# MCU.net
KiCad netlist of a schematic drawn in Altium Designer
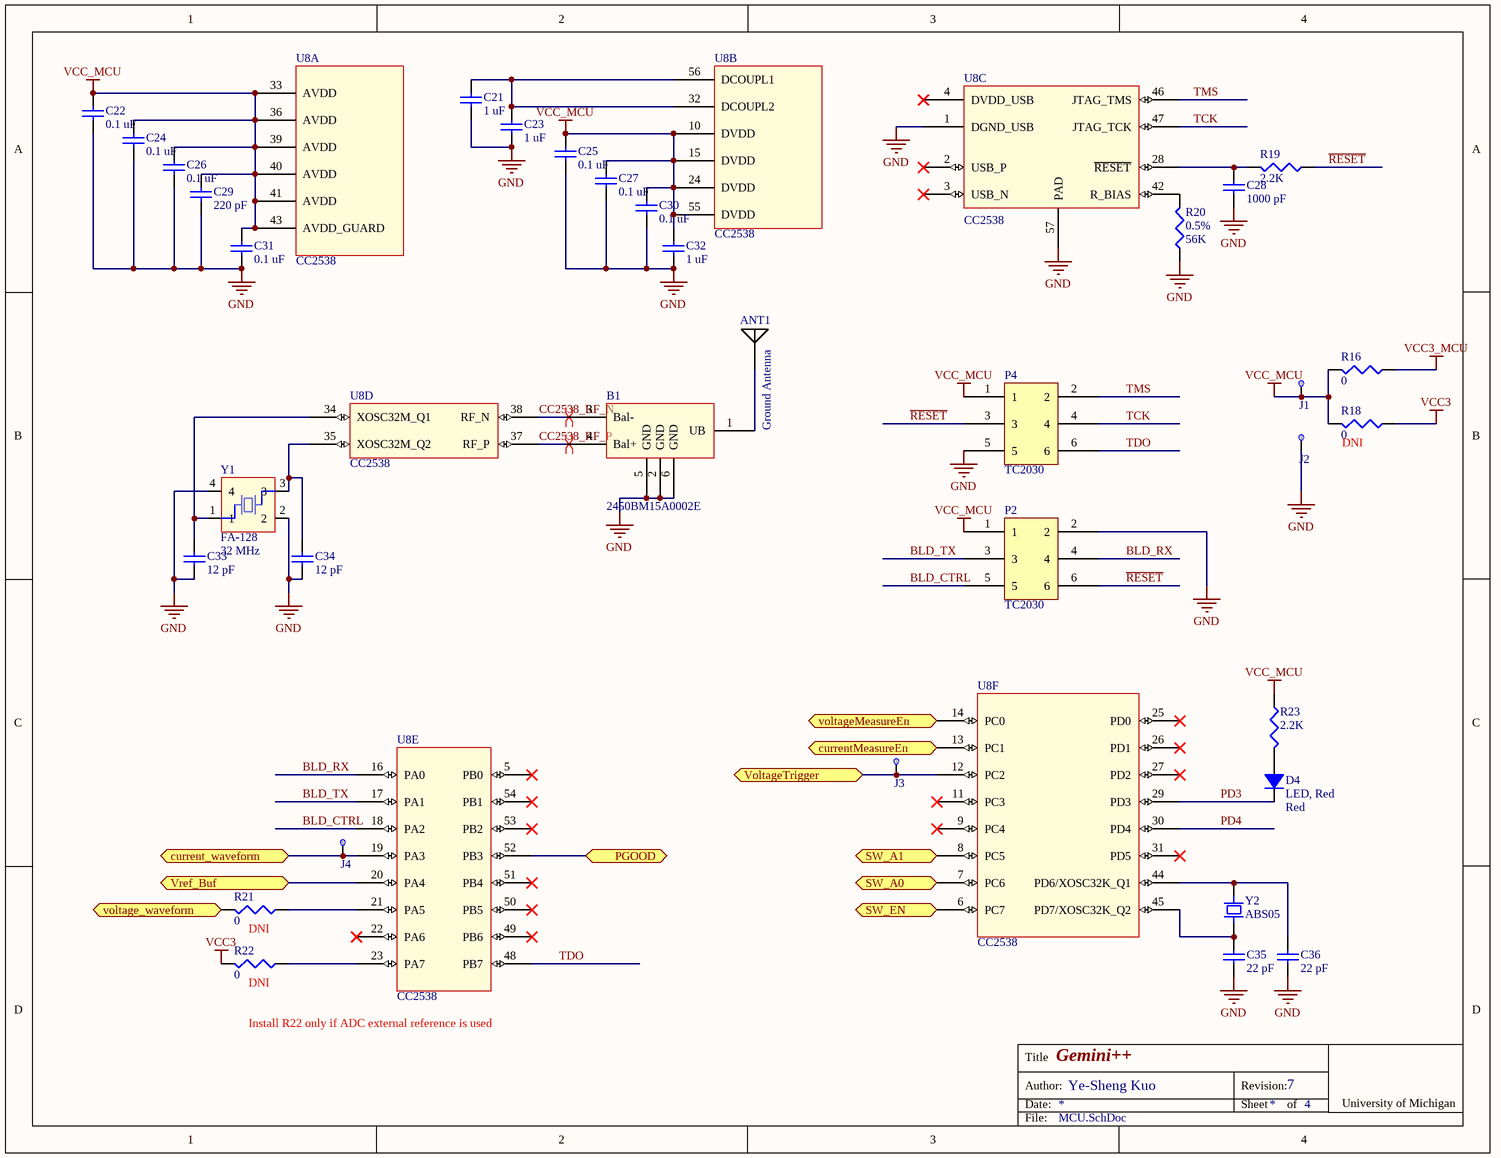
[diagram p0: MCU.SchDoc]

(export (version "E")
  (design (tool "Eeschema 10.0.6"))
  (components
    (comp (ref "ANT1")
      (value "Ground Antenna")
      (footprint "Chip Antenna")
      (description "2.4GHz Surface Mount Device (SMD) On Ground Antenna, 50 Ohms")
      (libsource (lib "RF") (part "Ground Antenna"))
    )
    (comp (ref "B1")
      (value "2450BM15A0002E")
      (footprint "2450BM15A0002")
      (description "2.45 GHz Balun for TI CC253X")
      (libsource (lib "RF") (part "2450BM15A0002E"))
    )
    (comp (ref "C21")
      (value "1 uF")
      (footprint "0402")
      (description "Ceramic capacitor, 1 uF, 16V, 0402 package")
      (fields (field (name "TOLERANCE") "10%") (field (name "Comment") "Ceramic capacitor"))
      (libsource (lib "rlc") (part "C_1u_16V_0402_ceramic"))
    )
    (comp (ref "C22")
      (value "0.1 uF")
      (footprint "0402")
      (description "Ceramic capacitor, 0.1u, 0402 package")
      (fields (field (name "TOLERANCE") "10%") (field (name "Comment") "Ceramic capacitor"))
      (libsource (lib "rlc") (part "C_0.1u_10V_0402_ceramic"))
    )
    (comp (ref "C23")
      (value "1 uF")
      (footprint "0402")
      (description "Ceramic capacitor, 1 uF, 16V, 0402 package")
      (fields (field (name "TOLERANCE") "10%") (field (name "Comment") "Ceramic capacitor"))
      (libsource (lib "rlc") (part "C_1u_16V_0402_ceramic"))
    )
    (comp (ref "C24")
      (value "0.1 uF")
      (footprint "0402")
      (description "Ceramic capacitor, 0.1u, 0402 package")
      (fields (field (name "TOLERANCE") "10%") (field (name "Comment") "Ceramic capacitor"))
      (libsource (lib "rlc") (part "C_0.1u_10V_0402_ceramic"))
    )
    (comp (ref "C25")
      (value "0.1 uF")
      (footprint "0402")
      (description "Ceramic capacitor, 0.1u, 0402 package")
      (fields (field (name "TOLERANCE") "10%") (field (name "Comment") "Ceramic capacitor"))
      (libsource (lib "rlc") (part "C_0.1u_10V_0402_ceramic"))
    )
    (comp (ref "C26")
      (value "0.1 uF")
      (footprint "0402")
      (description "Ceramic capacitor, 0.1u, 0402 package")
      (fields (field (name "TOLERANCE") "10%") (field (name "Comment") "Ceramic capacitor"))
      (libsource (lib "rlc") (part "C_0.1u_10V_0402_ceramic"))
    )
    (comp (ref "C27")
      (value "0.1 uF")
      (footprint "0402")
      (description "Ceramic capacitor, 0.1u, 0402 package")
      (fields (field (name "TOLERANCE") "10%") (field (name "Comment") "Ceramic capacitor"))
      (libsource (lib "rlc") (part "C_0.1u_10V_0402_ceramic"))
    )
    (comp (ref "C28")
      (value "1000 pF")
      (footprint "0402")
      (description "Ceramic capacitor, 1000 pF, 0402 package")
      (fields (field (name "TOLERANCE") "10%") (field (name "Comment") "Ceramic capacitor"))
      (libsource (lib "rlc") (part "C_1000p_50V_0402_ceramic"))
    )
    (comp (ref "C29")
      (value "220 pF")
      (footprint "0402")
      (description "Ceramic capacitor, 220 pF, 0402 package")
      (fields (field (name "TOLERANCE") "10%") (field (name "Comment") "Ceramic capacitor"))
      (libsource (lib "rlc") (part "C_220p_50V_0402_ceramic"))
    )
    (comp (ref "C30")
      (value "0.1 uF")
      (footprint "0402")
      (description "Ceramic capacitor, 0.1u, 0402 package")
      (fields (field (name "TOLERANCE") "10%") (field (name "Comment") "Ceramic capacitor"))
      (libsource (lib "rlc") (part "C_0.1u_10V_0402_ceramic"))
    )
    (comp (ref "C31")
      (value "0.1 uF")
      (footprint "0402")
      (description "Ceramic capacitor, 0.1u, 0402 package")
      (fields (field (name "TOLERANCE") "10%") (field (name "Comment") "Ceramic capacitor"))
      (libsource (lib "rlc") (part "C_0.1u_10V_0402_ceramic"))
    )
    (comp (ref "C32")
      (value "1 uF")
      (footprint "0402")
      (description "Ceramic capacitor, 1 uF, 16V, 0402 package")
      (fields (field (name "TOLERANCE") "10%") (field (name "Comment") "Ceramic capacitor"))
      (libsource (lib "rlc") (part "C_1u_16V_0402_ceramic"))
    )
    (comp (ref "C33")
      (value "12 pF")
      (footprint "0402")
      (description "Ceramic capacitor, 12 pF, 0402 package")
      (fields (field (name "TOLERANCE") "2%") (field (name "Comment") "Ceramic capacitor"))
      (libsource (lib "rlc") (part "C_12p_0402_ceramic"))
    )
    (comp (ref "C34")
      (value "12 pF")
      (footprint "0402")
      (description "Ceramic capacitor, 12 pF, 0402 package")
      (fields (field (name "TOLERANCE") "2%") (field (name "Comment") "Ceramic capacitor"))
      (libsource (lib "rlc") (part "C_12p_0402_ceramic"))
    )
    (comp (ref "C35")
      (value "22 pF")
      (footprint "0402")
      (description "Ceramic capacitor, 22 pF, 0402 package")
      (fields (field (name "TOLERANCE") "2%") (field (name "Comment") "Ceramic capacitor"))
      (libsource (lib "rlc") (part "C_22p_0402_ceramic"))
    )
    (comp (ref "C36")
      (value "22 pF")
      (footprint "0402")
      (description "Ceramic capacitor, 22 pF, 0402 package")
      (fields (field (name "TOLERANCE") "2%") (field (name "Comment") "Ceramic capacitor"))
      (libsource (lib "rlc") (part "C_22p_0402_ceramic"))
    )
    (comp (ref "D4")
      (value "LED, Red")
      (footprint "0402 - DIODE")
      (description "LED, Red, 0402")
      (fields (field (name "COLOR") "Red"))
      (libsource (lib "rlc") (part "D_LED_RED_0402"))
    )
    (comp (ref "J1")
      (value "RCU 0603 SMD Testpoint")
      (footprint "RCU_0603")
      (description "0603 SMD Testpoint")
      (libsource (lib "connectors") (part "Testpoint-0603"))
    )
    (comp (ref "J2")
      (value "RCU 0603 SMD Testpoint")
      (footprint "RCU_0603")
      (description "0603 SMD Testpoint")
      (libsource (lib "connectors") (part "Testpoint-0603"))
    )
    (comp (ref "J3")
      (value "RCU 0603 SMD Testpoint")
      (footprint "RCU_0603")
      (description "0603 SMD Testpoint")
      (libsource (lib "connectors") (part "Testpoint-0603"))
    )
    (comp (ref "J4")
      (value "RCU 0603 SMD Testpoint")
      (footprint "RCU_0603")
      (description "0603 SMD Testpoint")
      (libsource (lib "connectors") (part "Testpoint-0603"))
    )
    (comp (ref "P2")
      (value "TC2030")
      (footprint "TC2030-IDC-NLFP")
      (description "TC2030-MCP-NL")
      (libsource (lib "connectors") (part "TC2030"))
    )
    (comp (ref "P4")
      (value "TC2030")
      (footprint "TC2030-IDC-NLFP")
      (description "TC2030-MCP-NL")
      (libsource (lib "connectors") (part "TC2030"))
    )
    (comp (ref "R16")
      (value "0")
      (footprint "0603")
      (description "Chip resistor, 0, 0603 package")
      (fields (field (name "Comment") "Chip resistor"))
      (libsource (lib "rlc") (part "R_0_0603"))
    )
    (comp (ref "R18")
      (value "0")
      (footprint "0603")
      (description "Chip resistor, 0, 0603 package")
      (fields (field (name "Comment") "Chip resistor"))
      (libsource (lib "rlc") (part "R_0_0603"))
    )
    (comp (ref "R19")
      (value "2.2K")
      (footprint "0402")
      (description "Chip resistor, 2.2K, 0402 package")
      (fields (field (name "TOLERANCE") "1%") (field (name "POWER") "1/16 W"))
      (libsource (lib "rlc") (part "R_2.2K_0402"))
    )
    (comp (ref "R20")
      (value "56K")
      (footprint "0402")
      (description "Chip resistor, 56K, 0402 package")
      (fields
        (field (name "POWER") "1/16 W")
        (field (name "TOLERANCE") "0.5%")
        (field (name "Comment") "Chip resistor")
      )
      (libsource (lib "rlc") (part "R_56K_0402"))
    )
    (comp (ref "R21")
      (value "0")
      (footprint "0402")
      (description "Chip resistor, 0, 0402 package")
      (fields (field (name "Comment") "Chip resistor"))
      (libsource (lib "rlc") (part "R_0_0402"))
    )
    (comp (ref "R22")
      (value "0")
      (footprint "0402")
      (description "Chip resistor, 0, 0402 package")
      (fields (field (name "Comment") "Chip resistor"))
      (libsource (lib "rlc") (part "R_0_0402"))
    )
    (comp (ref "R23")
      (value "2.2K")
      (footprint "0402")
      (description "Chip resistor, 2.2K, 0402 package")
      (fields (field (name "TOLERANCE") "1%") (field (name "POWER") "1/16 W"))
      (libsource (lib "rlc") (part "R_2.2K_0402"))
    )
    (comp (ref "U8")
      (value "CC2538")
      (footprint "QFN56")
      (description "A Powerful System-On-Chip for 2.4-GHz IEEE 802.15.4, 6LoWPAN  and ZigBee Applications")
      (libsource (lib "sdl") (part "CC2538"))
    )
    (comp (ref "Y1")
      (value "FA-128")
      (footprint "FA-128")
      (description "MHz Range Crystal Unit")
      (fields (field (name "FREQUENCY") "32 MHz"))
      (libsource (lib "crystal_oscillators_rtc") (part "FA-128"))
    )
    (comp (ref "Y2")
      (value "ABS05")
      (footprint "ABS05")
      (description "32768 Hz SMD Low profile crystal")
      (libsource (lib "crystal_oscillators_rtc") (part "ABS05"))
    )
  )
  (nets
    (net (code "1") (name "/BLD_CTRL") (class "Default")
      (node (ref "P2") (pin "5") (pinfunction "5_5") (pintype "passive"))
      (node (ref "U8") (pin "18") (pinfunction "PA2_18") (pintype "bidirectional"))
    )
    (net (code "2") (name "/BLD_RX") (class "Default")
      (node (ref "P2") (pin "4") (pinfunction "4_4") (pintype "passive"))
      (node (ref "U8") (pin "16") (pinfunction "PA0_16") (pintype "bidirectional"))
    )
    (net (code "3") (name "/BLD_TX") (class "Default")
      (node (ref "P2") (pin "3") (pinfunction "3_3") (pintype "passive"))
      (node (ref "U8") (pin "17") (pinfunction "PA1_17") (pintype "bidirectional"))
    )
    (net (code "4") (name "/CC2538_RF_N") (class "Default")
      (node (ref "B1") (pin "3") (pinfunction "Bal-_3") (pintype "passive"))
      (node (ref "U8") (pin "38") (pinfunction "RF_N_38") (pintype "bidirectional"))
    )
    (net (code "5") (name "/CC2538_RF_P") (class "Default")
      (node (ref "B1") (pin "4") (pinfunction "Bal+_4") (pintype "passive"))
      (node (ref "U8") (pin "37") (pinfunction "RF_P_37") (pintype "bidirectional"))
    )
    (net (code "6") (name "/PD3") (class "Default")
      (node (ref "D4") (pin "2") (pintype "passive"))
      (node (ref "U8") (pin "29") (pinfunction "PD3_29") (pintype "bidirectional"))
    )
    (net (code "7") (name "/PD4") (class "Default")
      (node (ref "U8") (pin "30") (pinfunction "PD4_30") (pintype "bidirectional"))
    )
    (net (code "8") (name "/PGOOD") (class "Default")
      (node (ref "U8") (pin "52") (pinfunction "PB3_52") (pintype "bidirectional"))
    )
    (net (code "9") (name "/SW_A0") (class "Default")
      (node (ref "U8") (pin "7") (pinfunction "PC6_7") (pintype "bidirectional"))
    )
    (net (code "10") (name "/SW_A1") (class "Default")
      (node (ref "U8") (pin "8") (pinfunction "PC5_8") (pintype "bidirectional"))
    )
    (net (code "11") (name "/SW_EN") (class "Default")
      (node (ref "U8") (pin "6") (pinfunction "PC7_6") (pintype "bidirectional"))
    )
    (net (code "12") (name "/TCK") (class "Default")
      (node (ref "P4") (pin "4") (pinfunction "4_4") (pintype "passive"))
      (node (ref "U8") (pin "47") (pinfunction "JTAG_TCK_47") (pintype "bidirectional"))
    )
    (net (code "13") (name "/TDO") (class "Default")
      (node (ref "P4") (pin "6") (pinfunction "6_6") (pintype "passive"))
      (node (ref "U8") (pin "48") (pinfunction "PB7_48") (pintype "bidirectional"))
    )
    (net (code "14") (name "/TMS") (class "Default")
      (node (ref "P4") (pin "2") (pinfunction "2_2") (pintype "passive"))
      (node (ref "U8") (pin "46") (pinfunction "JTAG_TMS_46") (pintype "bidirectional"))
    )
    (net (code "15") (name "/VoltageTrigger") (class "Default")
      (node (ref "J3") (pin "1") (pinfunction "TB_1") (pintype "passive"))
      (node (ref "U8") (pin "12") (pinfunction "PC2_12") (pintype "bidirectional"))
    )
    (net (code "16") (name "/Vref_Buf") (class "Default")
      (node (ref "U8") (pin "20") (pinfunction "PA4_20") (pintype "bidirectional"))
    )
    (net (code "17") (name "/currentMeasureEn") (class "Default")
      (node (ref "U8") (pin "13") (pinfunction "PC1_13") (pintype "bidirectional"))
    )
    (net (code "18") (name "/current_waveform") (class "Default")
      (node (ref "J4") (pin "1") (pinfunction "TB_1") (pintype "passive"))
      (node (ref "U8") (pin "19") (pinfunction "PA3_19") (pintype "bidirectional"))
    )
    (net (code "19") (name "/voltageMeasureEn") (class "Default")
      (node (ref "U8") (pin "14") (pinfunction "PC0_14") (pintype "bidirectional"))
    )
    (net (code "20") (name "/voltage_waveform") (class "Default")
      (node (ref "R21") (pin "1") (pintype "passive"))
    )
    (net (code "21") (name "/~{RESET}") (class "Default")
      (node (ref "P2") (pin "6") (pinfunction "6_6") (pintype "passive"))
      (node (ref "P4") (pin "3") (pinfunction "3_3") (pintype "passive"))
      (node (ref "R19") (pin "2") (pintype "passive"))
    )
    (net (code "22") (name "GND") (class "Default")
      (node (ref "B1") (pin "2") (pinfunction "GND_2") (pintype "passive"))
      (node (ref "B1") (pin "5") (pinfunction "GND_5") (pintype "passive"))
      (node (ref "B1") (pin "6") (pinfunction "GND_6") (pintype "passive"))
      (node (ref "C21") (pin "2") (pintype "passive"))
      (node (ref "C22") (pin "2") (pintype "passive"))
      (node (ref "C23") (pin "2") (pintype "passive"))
      (node (ref "C24") (pin "2") (pintype "passive"))
      (node (ref "C25") (pin "2") (pintype "passive"))
      (node (ref "C26") (pin "2") (pintype "passive"))
      (node (ref "C27") (pin "2") (pintype "passive"))
      (node (ref "C28") (pin "2") (pintype "passive"))
      (node (ref "C29") (pin "2") (pintype "passive"))
      (node (ref "C30") (pin "2") (pintype "passive"))
      (node (ref "C31") (pin "2") (pintype "passive"))
      (node (ref "C32") (pin "2") (pintype "passive"))
      (node (ref "C33") (pin "1") (pintype "passive"))
      (node (ref "C34") (pin "1") (pintype "passive"))
      (node (ref "C35") (pin "2") (pintype "passive"))
      (node (ref "C36") (pin "2") (pintype "passive"))
      (node (ref "J2") (pin "1") (pinfunction "TB_1") (pintype "passive"))
      (node (ref "P2") (pin "2") (pinfunction "2_2") (pintype "passive"))
      (node (ref "P4") (pin "5") (pinfunction "5_5") (pintype "passive"))
      (node (ref "R20") (pin "2") (pintype "passive"))
      (node (ref "U8") (pin "1") (pinfunction "DGND_USB_1") (pintype "power_in"))
      (node (ref "U8") (pin "57") (pinfunction "PAD_57") (pintype "power_in"))
      (node (ref "Y1") (pin "2") (pinfunction "2_2") (pintype "passive"))
      (node (ref "Y1") (pin "4") (pinfunction "4_4") (pintype "passive"))
    )
    (net (code "23") (name "Net-(B1-UB)") (class "Default")
      (node (ref "ANT1") (pin "1") (pintype "passive"))
      (node (ref "B1") (pin "1") (pinfunction "UB_1") (pintype "passive"))
    )
    (net (code "24") (name "Net-(D4-Pad1)") (class "Default")
      (node (ref "D4") (pin "1") (pintype "passive"))
      (node (ref "R23") (pin "1") (pintype "passive"))
    )
    (net (code "25") (name "Net-(U8B-DCOUPL1)") (class "Default")
      (node (ref "C21") (pin "1") (pintype "passive"))
      (node (ref "C23") (pin "1") (pintype "passive"))
      (node (ref "U8") (pin "32") (pinfunction "DCOUPL2_32") (pintype "power_in"))
      (node (ref "U8") (pin "56") (pinfunction "DCOUPL1_56") (pintype "power_in"))
    )
    (net (code "26") (name "Net-(U8C-R_BIAS)") (class "Default")
      (node (ref "R20") (pin "1") (pintype "passive"))
      (node (ref "U8") (pin "42") (pinfunction "R_BIAS_42") (pintype "bidirectional"))
    )
    (net (code "27") (name "Net-(U8C-~{RESET})") (class "Default")
      (node (ref "C28") (pin "1") (pintype "passive"))
      (node (ref "R19") (pin "1") (pintype "passive"))
      (node (ref "U8") (pin "28") (pinfunction "~{RESET}_28") (pintype "bidirectional"))
    )
    (net (code "28") (name "Net-(U8D-XOSC32M_Q1)") (class "Default")
      (node (ref "C33") (pin "2") (pintype "passive"))
      (node (ref "U8") (pin "34") (pinfunction "XOSC32M_Q1_34") (pintype "bidirectional"))
      (node (ref "Y1") (pin "1") (pinfunction "1_1") (pintype "passive"))
    )
    (net (code "29") (name "Net-(U8D-XOSC32M_Q2)") (class "Default")
      (node (ref "C34") (pin "2") (pintype "passive"))
      (node (ref "U8") (pin "35") (pinfunction "XOSC32M_Q2_35") (pintype "bidirectional"))
      (node (ref "Y1") (pin "3") (pinfunction "3_3") (pintype "passive"))
    )
    (net (code "30") (name "Net-(U8E-PA5)") (class "Default")
      (node (ref "R21") (pin "2") (pintype "passive"))
      (node (ref "U8") (pin "21") (pinfunction "PA5_21") (pintype "bidirectional"))
    )
    (net (code "31") (name "Net-(U8E-PA7)") (class "Default")
      (node (ref "R22") (pin "2") (pintype "passive"))
      (node (ref "U8") (pin "23") (pinfunction "PA7_23") (pintype "bidirectional"))
    )
    (net (code "32") (name "Net-(U8F-PD6{slash}XOSC32K_Q1)") (class "Default")
      (node (ref "C36") (pin "1") (pintype "passive"))
      (node (ref "U8") (pin "44") (pinfunction "PD6/XOSC32K_Q1_44") (pintype "bidirectional"))
      (node (ref "Y2") (pin "1") (pintype "passive"))
    )
    (net (code "33") (name "Net-(U8F-PD7{slash}XOSC32K_Q2)") (class "Default")
      (node (ref "C35") (pin "1") (pintype "passive"))
      (node (ref "U8") (pin "45") (pinfunction "PD7/XOSC32K_Q2_45") (pintype "bidirectional"))
      (node (ref "Y2") (pin "2") (pintype "passive"))
    )
    (net (code "34") (name "VCC3") (class "Default")
      (node (ref "R18") (pin "2") (pintype "passive"))
      (node (ref "R22") (pin "1") (pintype "passive"))
    )
    (net (code "35") (name "VCC3_MCU") (class "Default") (node (ref "R16") (pin "2") (pintype "passive")))
    (net (code "36") (name "VCC_MCU") (class "Default")
      (node (ref "C22") (pin "1") (pintype "passive"))
      (node (ref "C24") (pin "1") (pintype "passive"))
      (node (ref "C25") (pin "1") (pintype "passive"))
      (node (ref "C26") (pin "1") (pintype "passive"))
      (node (ref "C27") (pin "1") (pintype "passive"))
      (node (ref "C29") (pin "1") (pintype "passive"))
      (node (ref "C30") (pin "1") (pintype "passive"))
      (node (ref "C31") (pin "1") (pintype "passive"))
      (node (ref "C32") (pin "1") (pintype "passive"))
      (node (ref "J1") (pin "1") (pinfunction "TB_1") (pintype "passive"))
      (node (ref "P2") (pin "1") (pinfunction "1_1") (pintype "passive"))
      (node (ref "P4") (pin "1") (pinfunction "1_1") (pintype "passive"))
      (node (ref "R16") (pin "1") (pintype "passive"))
      (node (ref "R18") (pin "1") (pintype "passive"))
      (node (ref "R23") (pin "2") (pintype "passive"))
      (node (ref "U8") (pin "10") (pinfunction "DVDD_10") (pintype "power_in"))
      (node (ref "U8") (pin "15") (pinfunction "DVDD_15") (pintype "power_in"))
      (node (ref "U8") (pin "24") (pinfunction "DVDD_24") (pintype "power_in"))
      (node (ref "U8") (pin "33") (pinfunction "AVDD_33") (pintype "power_in"))
      (node (ref "U8") (pin "36") (pinfunction "AVDD_36") (pintype "power_in"))
      (node (ref "U8") (pin "39") (pinfunction "AVDD_39") (pintype "power_in"))
      (node (ref "U8") (pin "40") (pinfunction "AVDD_40") (pintype "power_in"))
      (node (ref "U8") (pin "41") (pinfunction "AVDD_41") (pintype "power_in"))
      (node (ref "U8") (pin "43") (pinfunction "AVDD_GUARD_43") (pintype "power_in"))
      (node (ref "U8") (pin "55") (pinfunction "DVDD_55") (pintype "power_in"))
    )
    (net (code "37") (name "unconnected-(U8C-DVDD_USB-Pad4)") (class "Default")
      (node (ref "U8") (pin "4") (pinfunction "DVDD_USB_4") (pintype "power_in+no_connect"))
    )
    (net (code "38") (name "unconnected-(U8C-USB_N-Pad3)") (class "Default")
      (node (ref "U8") (pin "3") (pinfunction "USB_N_3") (pintype "bidirectional+no_connect"))
    )
    (net (code "39") (name "unconnected-(U8C-USB_P-Pad2)") (class "Default")
      (node (ref "U8") (pin "2") (pinfunction "USB_P_2") (pintype "bidirectional+no_connect"))
    )
    (net (code "40") (name "unconnected-(U8E-PA6-Pad22)") (class "Default")
      (node (ref "U8") (pin "22") (pinfunction "PA6_22") (pintype "bidirectional+no_connect"))
    )
    (net (code "41") (name "unconnected-(U8E-PB0-Pad5)") (class "Default")
      (node (ref "U8") (pin "5") (pinfunction "PB0_5") (pintype "bidirectional+no_connect"))
    )
    (net (code "42") (name "unconnected-(U8E-PB1-Pad54)") (class "Default")
      (node (ref "U8") (pin "54") (pinfunction "PB1_54") (pintype "bidirectional+no_connect"))
    )
    (net (code "43") (name "unconnected-(U8E-PB2-Pad53)") (class "Default")
      (node (ref "U8") (pin "53") (pinfunction "PB2_53") (pintype "bidirectional+no_connect"))
    )
    (net (code "44") (name "unconnected-(U8E-PB4-Pad51)") (class "Default")
      (node (ref "U8") (pin "51") (pinfunction "PB4_51") (pintype "bidirectional+no_connect"))
    )
    (net (code "45") (name "unconnected-(U8E-PB5-Pad50)") (class "Default")
      (node (ref "U8") (pin "50") (pinfunction "PB5_50") (pintype "bidirectional+no_connect"))
    )
    (net (code "46") (name "unconnected-(U8E-PB6-Pad49)") (class "Default")
      (node (ref "U8") (pin "49") (pinfunction "PB6_49") (pintype "bidirectional+no_connect"))
    )
    (net (code "47") (name "unconnected-(U8F-PC3-Pad11)") (class "Default")
      (node (ref "U8") (pin "11") (pinfunction "PC3_11") (pintype "bidirectional+no_connect"))
    )
    (net (code "48") (name "unconnected-(U8F-PC4-Pad9)") (class "Default")
      (node (ref "U8") (pin "9") (pinfunction "PC4_9") (pintype "bidirectional+no_connect"))
    )
    (net (code "49") (name "unconnected-(U8F-PD0-Pad25)") (class "Default")
      (node (ref "U8") (pin "25") (pinfunction "PD0_25") (pintype "bidirectional+no_connect"))
    )
    (net (code "50") (name "unconnected-(U8F-PD1-Pad26)") (class "Default")
      (node (ref "U8") (pin "26") (pinfunction "PD1_26") (pintype "bidirectional+no_connect"))
    )
    (net (code "51") (name "unconnected-(U8F-PD2-Pad27)") (class "Default")
      (node (ref "U8") (pin "27") (pinfunction "PD2_27") (pintype "bidirectional+no_connect"))
    )
    (net (code "52") (name "unconnected-(U8F-PD5-Pad31)") (class "Default")
      (node (ref "U8") (pin "31") (pinfunction "PD5_31") (pintype "bidirectional+no_connect"))
    )
  )
)
